# Redundancy.net
KiCad netlist of a schematic drawn in EAGLE
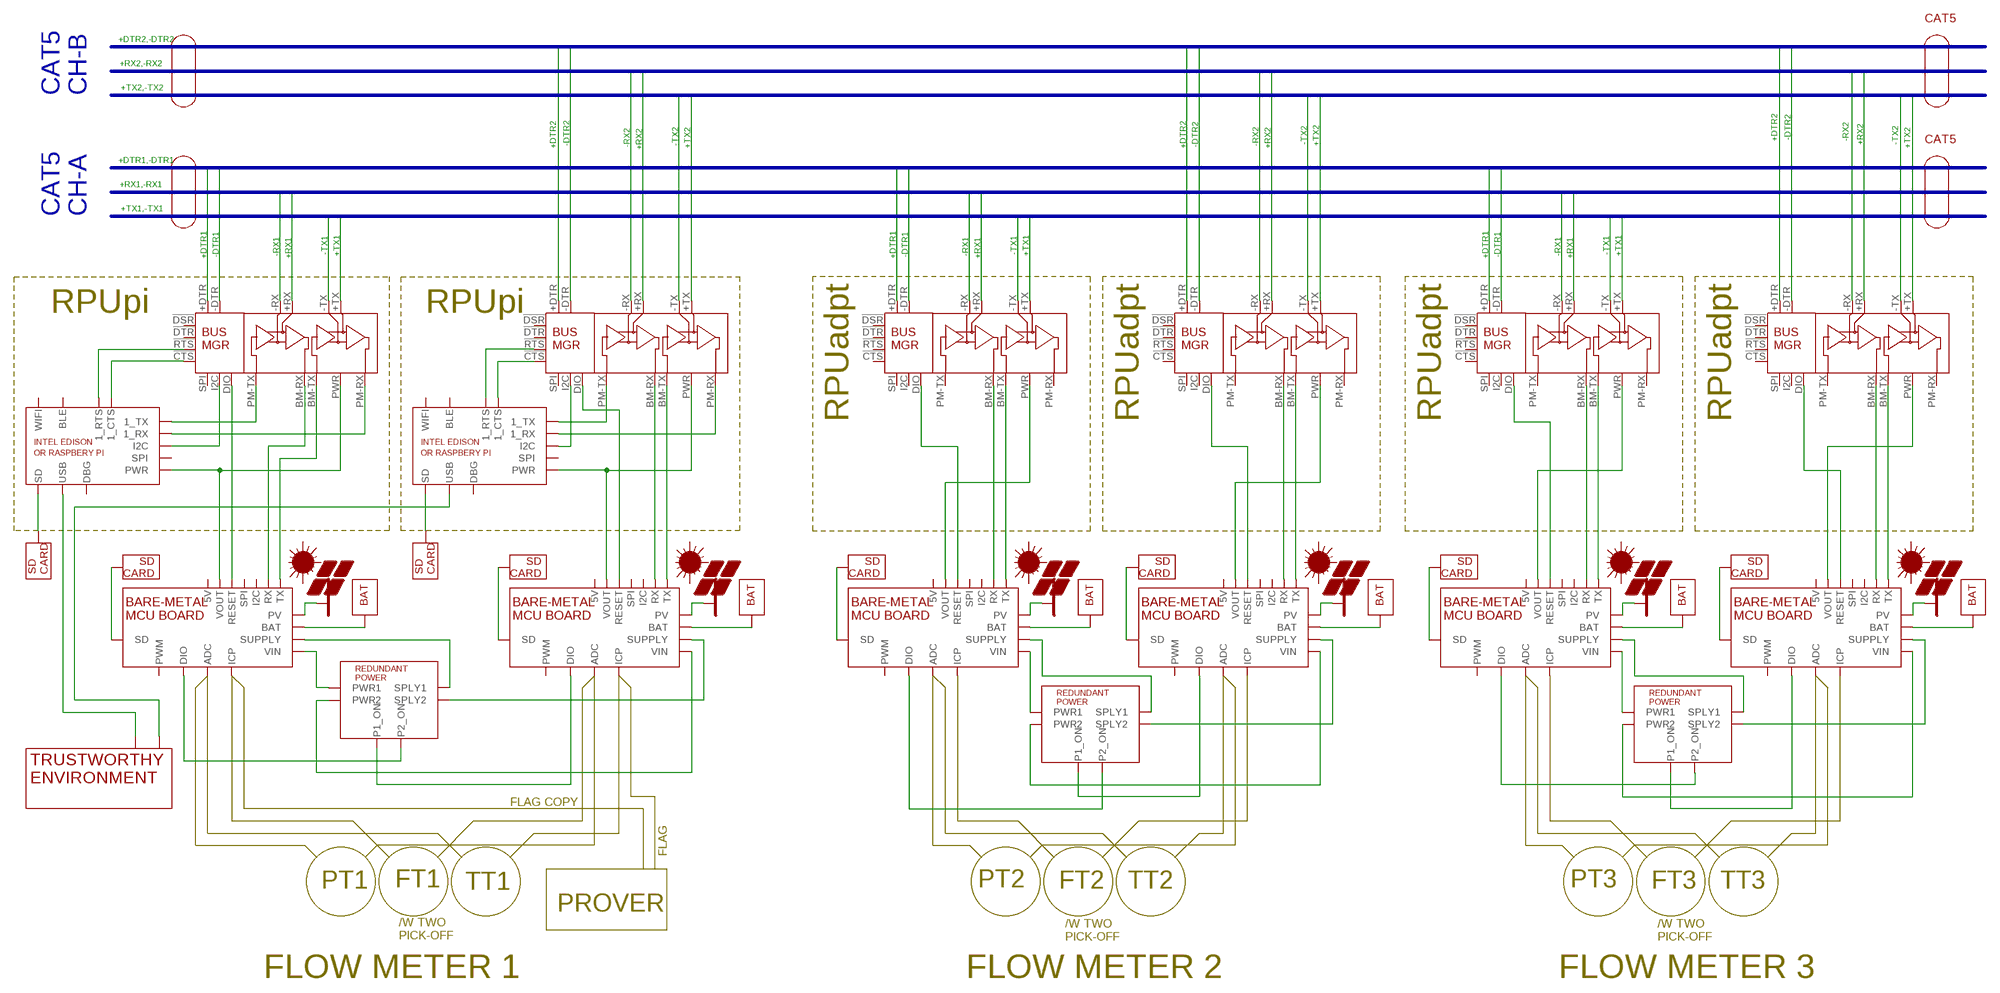
[diagram p0: schematic, sheet 1]

(export (version "E")
  (design (tool "Eeschema 10.0.6"))
  (components
    (comp (ref "BM1")
      (value "BARE-METAL")
      (footprint "eagle-import:NA-20")
      (libsource (lib "eagle-import") (part "BARE-METAL"))
    )
    (comp (ref "BM2")
      (value "BARE-METAL")
      (footprint "eagle-import:NA-20")
      (libsource (lib "eagle-import") (part "BARE-METAL"))
    )
    (comp (ref "BM3")
      (value "BARE-METAL")
      (footprint "eagle-import:NA-20")
      (libsource (lib "eagle-import") (part "BARE-METAL"))
    )
    (comp (ref "BM4")
      (value "BARE-METAL")
      (footprint "eagle-import:NA-20")
      (libsource (lib "eagle-import") (part "BARE-METAL"))
    )
    (comp (ref "BM5")
      (value "BARE-METAL")
      (footprint "eagle-import:NA-20")
      (libsource (lib "eagle-import") (part "BARE-METAL"))
    )
    (comp (ref "BM6")
      (value "BARE-METAL")
      (footprint "eagle-import:NA-20")
      (libsource (lib "eagle-import") (part "BARE-METAL"))
    )
    (comp (ref "PM1")
      (value "TRUSTWORTHY")
      (footprint "eagle-import:NA-20")
      (libsource (lib "eagle-import") (part "TRUSTWORTHY"))
    )
    (comp (ref "PV1")
      (value "PV")
      (footprint "eagle-import:NA-20")
      (libsource (lib "eagle-import") (part "PV"))
    )
    (comp (ref "PV2")
      (value "PV")
      (footprint "eagle-import:NA-20")
      (libsource (lib "eagle-import") (part "PV"))
    )
    (comp (ref "PV3")
      (value "PV")
      (footprint "eagle-import:NA-20")
      (libsource (lib "eagle-import") (part "PV"))
    )
    (comp (ref "PV4")
      (value "PV")
      (footprint "eagle-import:NA-20")
      (libsource (lib "eagle-import") (part "PV"))
    )
    (comp (ref "PV5")
      (value "PV")
      (footprint "eagle-import:NA-20")
      (libsource (lib "eagle-import") (part "PV"))
    )
    (comp (ref "PV6")
      (value "PV")
      (footprint "eagle-import:NA-20")
      (libsource (lib "eagle-import") (part "PV"))
    )
    (comp (ref "SD1")
      (value "SD")
      (footprint "eagle-import:NA-20")
      (libsource (lib "eagle-import") (part "SD"))
    )
    (comp (ref "SD2")
      (value "SD")
      (footprint "eagle-import:NA-20")
      (libsource (lib "eagle-import") (part "SD"))
    )
    (comp (ref "SD3")
      (value "SD")
      (footprint "eagle-import:NA-20")
      (libsource (lib "eagle-import") (part "SD"))
    )
    (comp (ref "SD4")
      (value "SD")
      (footprint "eagle-import:NA-20")
      (libsource (lib "eagle-import") (part "SD"))
    )
    (comp (ref "SD5")
      (value "SD")
      (footprint "eagle-import:NA-20")
      (libsource (lib "eagle-import") (part "SD"))
    )
    (comp (ref "SD6")
      (value "SD")
      (footprint "eagle-import:NA-20")
      (libsource (lib "eagle-import") (part "SD"))
    )
    (comp (ref "SD7")
      (value "SD")
      (footprint "eagle-import:NA-20")
      (libsource (lib "eagle-import") (part "SD"))
    )
    (comp (ref "SD8")
      (value "SD")
      (footprint "eagle-import:NA-20")
      (libsource (lib "eagle-import") (part "SD"))
    )
    (comp (ref "U$1")
      (value "BUS_MGR")
      (footprint "eagle-import:NA-10_WITH_RPU_NAMES")
      (libsource (lib "eagle-import") (part "BUS_MGR"))
    )
    (comp (ref "U$2")
      (value "BUS_MGR")
      (footprint "eagle-import:NA-10_WITH_RPU_NAMES")
      (libsource (lib "eagle-import") (part "BUS_MGR"))
    )
    (comp (ref "U$3")
      (value "BUS_MGR")
      (footprint "eagle-import:NA-10_WITH_RPU_NAMES")
      (libsource (lib "eagle-import") (part "BUS_MGR"))
    )
    (comp (ref "U$4")
      (value "BUS_MGR")
      (footprint "eagle-import:NA-10_WITH_RPU_NAMES")
      (libsource (lib "eagle-import") (part "BUS_MGR"))
    )
    (comp (ref "U$5")
      (value "EDISON")
      (footprint "eagle-import:NA-20")
      (libsource (lib "eagle-import") (part "EDISON"))
    )
    (comp (ref "U$6")
      (value "EDISON")
      (footprint "eagle-import:NA-20")
      (libsource (lib "eagle-import") (part "EDISON"))
    )
    (comp (ref "U$7")
      (value "BAT")
      (footprint "eagle-import:NA-20")
      (libsource (lib "eagle-import") (part "BAT"))
    )
    (comp (ref "U$8")
      (value "BAT")
      (footprint "eagle-import:NA-20")
      (libsource (lib "eagle-import") (part "BAT"))
    )
    (comp (ref "U$9")
      (value "BAT")
      (footprint "eagle-import:NA-20")
      (libsource (lib "eagle-import") (part "BAT"))
    )
    (comp (ref "U$10")
      (value "BAT")
      (footprint "eagle-import:NA-20")
      (libsource (lib "eagle-import") (part "BAT"))
    )
    (comp (ref "U$11")
      (value "BUS_MGR")
      (footprint "eagle-import:NA-10_WITH_RPU_NAMES")
      (libsource (lib "eagle-import") (part "BUS_MGR"))
    )
    (comp (ref "U$12")
      (value "BUS_MGR")
      (footprint "eagle-import:NA-10_WITH_RPU_NAMES")
      (libsource (lib "eagle-import") (part "BUS_MGR"))
    )
    (comp (ref "U$13")
      (value "BAT")
      (footprint "eagle-import:NA-20")
      (libsource (lib "eagle-import") (part "BAT"))
    )
    (comp (ref "U$14")
      (value "BAT")
      (footprint "eagle-import:NA-20")
      (libsource (lib "eagle-import") (part "BAT"))
    )
    (comp (ref "U$15")
      (value "REDUNDANT_PWR")
      (footprint "eagle-import:NA-20")
      (libsource (lib "eagle-import") (part "REDUNDANT_PWR"))
    )
    (comp (ref "U$16")
      (value "REDUNDANT_PWR")
      (footprint "eagle-import:NA-20")
      (libsource (lib "eagle-import") (part "REDUNDANT_PWR"))
    )
    (comp (ref "U$17")
      (value "REDUNDANT_PWR")
      (footprint "eagle-import:NA-20")
      (libsource (lib "eagle-import") (part "REDUNDANT_PWR"))
    )
  )
  (nets
    (net (code "1") (name "/+DTR1") (class "Default")
      (node (ref "U$1") (pin "+DTR") (pinfunction "+DTR_+DTR") (pintype "bidirectional"))
      (node (ref "U$11") (pin "+DTR") (pinfunction "+DTR_+DTR") (pintype "bidirectional"))
      (node (ref "U$3") (pin "+DTR") (pinfunction "+DTR_+DTR") (pintype "bidirectional"))
    )
    (net (code "2") (name "/+DTR2") (class "Default")
      (node (ref "U$12") (pin "+DTR") (pinfunction "+DTR_+DTR") (pintype "bidirectional"))
      (node (ref "U$2") (pin "+DTR") (pinfunction "+DTR_+DTR") (pintype "bidirectional"))
      (node (ref "U$4") (pin "+DTR") (pinfunction "+DTR_+DTR") (pintype "bidirectional"))
    )
    (net (code "3") (name "/+RX1") (class "Default")
      (node (ref "U$1") (pin "+RX") (pinfunction "+RX_+RX") (pintype "bidirectional"))
      (node (ref "U$11") (pin "+RX") (pinfunction "+RX_+RX") (pintype "bidirectional"))
      (node (ref "U$3") (pin "+RX") (pinfunction "+RX_+RX") (pintype "bidirectional"))
    )
    (net (code "4") (name "/+RX2") (class "Default")
      (node (ref "U$12") (pin "+RX") (pinfunction "+RX_+RX") (pintype "bidirectional"))
      (node (ref "U$2") (pin "+RX") (pinfunction "+RX_+RX") (pintype "bidirectional"))
      (node (ref "U$4") (pin "+RX") (pinfunction "+RX_+RX") (pintype "bidirectional"))
    )
    (net (code "5") (name "/+TX1") (class "Default")
      (node (ref "U$1") (pin "+TX") (pinfunction "+TX_+TX") (pintype "bidirectional"))
      (node (ref "U$11") (pin "+TX") (pinfunction "+TX_+TX") (pintype "bidirectional"))
      (node (ref "U$3") (pin "+TX") (pinfunction "+TX_+TX") (pintype "bidirectional"))
    )
    (net (code "6") (name "/+TX2") (class "Default")
      (node (ref "U$12") (pin "+TX") (pinfunction "+TX_+TX") (pintype "bidirectional"))
      (node (ref "U$2") (pin "+TX") (pinfunction "+TX_+TX") (pintype "bidirectional"))
      (node (ref "U$4") (pin "+TX") (pinfunction "+TX_+TX") (pintype "bidirectional"))
    )
    (net (code "7") (name "/-DTR1") (class "Default")
      (node (ref "U$1") (pin "-DTR") (pinfunction "-DTR_-DTR") (pintype "bidirectional"))
      (node (ref "U$11") (pin "-DTR") (pinfunction "-DTR_-DTR") (pintype "bidirectional"))
      (node (ref "U$3") (pin "-DTR") (pinfunction "-DTR_-DTR") (pintype "bidirectional"))
    )
    (net (code "8") (name "/-DTR2") (class "Default")
      (node (ref "U$12") (pin "-DTR") (pinfunction "-DTR_-DTR") (pintype "bidirectional"))
      (node (ref "U$2") (pin "-DTR") (pinfunction "-DTR_-DTR") (pintype "bidirectional"))
      (node (ref "U$4") (pin "-DTR") (pinfunction "-DTR_-DTR") (pintype "bidirectional"))
    )
    (net (code "9") (name "/-RX1") (class "Default")
      (node (ref "U$1") (pin "-RX") (pinfunction "-RX_-RX") (pintype "bidirectional"))
      (node (ref "U$11") (pin "-RX") (pinfunction "-RX_-RX") (pintype "bidirectional"))
      (node (ref "U$3") (pin "-RX") (pinfunction "-RX_-RX") (pintype "bidirectional"))
    )
    (net (code "10") (name "/-RX2") (class "Default")
      (node (ref "U$12") (pin "-RX") (pinfunction "-RX_-RX") (pintype "bidirectional"))
      (node (ref "U$2") (pin "-RX") (pinfunction "-RX_-RX") (pintype "bidirectional"))
      (node (ref "U$4") (pin "-RX") (pinfunction "-RX_-RX") (pintype "bidirectional"))
    )
    (net (code "11") (name "/-TX1") (class "Default")
      (node (ref "U$1") (pin "-TX") (pinfunction "-TX_-TX") (pintype "bidirectional"))
      (node (ref "U$11") (pin "-TX") (pinfunction "-TX_-TX") (pintype "bidirectional"))
      (node (ref "U$3") (pin "-TX") (pinfunction "-TX_-TX") (pintype "bidirectional"))
    )
    (net (code "12") (name "/-TX2") (class "Default")
      (node (ref "U$12") (pin "-TX") (pinfunction "-TX_-TX") (pintype "bidirectional"))
      (node (ref "U$2") (pin "-TX") (pinfunction "-TX_-TX") (pintype "bidirectional"))
      (node (ref "U$4") (pin "-TX") (pinfunction "-TX_-TX") (pintype "bidirectional"))
    )
    (net (code "19") (name "Net-(BM1-BAT)") (class "Default")
      (node (ref "BM1") (pin "6") (pinfunction "BAT_6") (pintype "bidirectional"))
      (node (ref "U$10") (pin "1") (pinfunction "BAT_PWR_1") (pintype "bidirectional"))
    )
    (net (code "20") (name "Net-(BM1-DIO)") (class "Default")
      (node (ref "BM1") (pin "9") (pinfunction "DIO_9") (pintype "bidirectional"))
      (node (ref "U$16") (pin "1") (pinfunction "P1_ON_1") (pintype "input"))
    )
    (net (code "21") (name "Net-(BM1-PV)") (class "Default")
      (node (ref "BM1") (pin "5") (pinfunction "PV_5") (pintype "bidirectional"))
      (node (ref "PV4") (pin "1") (pinfunction "PV_PWR_1") (pintype "bidirectional"))
    )
    (net (code "22") (name "Net-(BM1-RESET)") (class "Default")
      (node (ref "BM1") (pin "13") (pinfunction "RESET_13") (pintype "bidirectional"))
      (node (ref "U$4") (pin "DIO") (pinfunction "DIO_DIO") (pintype "bidirectional"))
    )
    (net (code "23") (name "Net-(BM1-RX)") (class "Default")
      (node (ref "BM1") (pin "2") (pinfunction "RX_2") (pintype "bidirectional"))
      (node (ref "U$4") (pin "BM-RX") (pinfunction "BM_RX_BM-RX") (pintype "bidirectional"))
    )
    (net (code "24") (name "Net-(BM1-SD)") (class "Default")
      (node (ref "BM1") (pin "11") (pinfunction "SD_11") (pintype "bidirectional"))
      (node (ref "SD4") (pin "1") (pinfunction "PV_PWR_1") (pintype "bidirectional"))
    )
    (net (code "25") (name "Net-(BM1-SUPPLY)") (class "Default")
      (node (ref "BM1") (pin "14") (pinfunction "SUPPLY_14") (pintype "bidirectional"))
      (node (ref "U$16") (pin "6") (pinfunction "SPLY2_6") (pintype "bidirectional"))
    )
    (net (code "26") (name "Net-(BM1-TX)") (class "Default")
      (node (ref "BM1") (pin "1") (pinfunction "TX_1") (pintype "bidirectional"))
      (node (ref "U$4") (pin "BM-TX") (pinfunction "BM_TX_BM-TX") (pintype "bidirectional"))
    )
    (net (code "27") (name "Net-(BM1-VIN)") (class "Default")
      (node (ref "BM1") (pin "16") (pinfunction "VIN_16") (pintype "bidirectional"))
      (node (ref "U$16") (pin "4") (pinfunction "PWR2_4") (pintype "bidirectional"))
    )
    (net (code "28") (name "Net-(BM1-VOUT)") (class "Default")
      (node (ref "BM1") (pin "12") (pinfunction "VOUT_12") (pintype "bidirectional"))
      (node (ref "U$4") (pin "PWR") (pinfunction "PWR_PWR") (pintype "bidirectional"))
    )
    (net (code "29") (name "Net-(BM2-BAT)") (class "Default")
      (node (ref "BM2") (pin "6") (pinfunction "BAT_6") (pintype "bidirectional"))
      (node (ref "U$9") (pin "1") (pinfunction "BAT_PWR_1") (pintype "bidirectional"))
    )
    (net (code "30") (name "Net-(BM2-DIO)") (class "Default")
      (node (ref "BM2") (pin "9") (pinfunction "DIO_9") (pintype "bidirectional"))
      (node (ref "U$16") (pin "2") (pinfunction "P2_ON_2") (pintype "input"))
    )
    (net (code "31") (name "Net-(BM2-PV)") (class "Default")
      (node (ref "BM2") (pin "5") (pinfunction "PV_5") (pintype "bidirectional"))
      (node (ref "PV3") (pin "1") (pinfunction "PV_PWR_1") (pintype "bidirectional"))
    )
    (net (code "32") (name "Net-(BM2-RESET)") (class "Default")
      (node (ref "BM2") (pin "13") (pinfunction "RESET_13") (pintype "bidirectional"))
      (node (ref "U$3") (pin "DIO") (pinfunction "DIO_DIO") (pintype "bidirectional"))
    )
    (net (code "33") (name "Net-(BM2-RX)") (class "Default")
      (node (ref "BM2") (pin "2") (pinfunction "RX_2") (pintype "bidirectional"))
      (node (ref "U$3") (pin "BM-RX") (pinfunction "BM_RX_BM-RX") (pintype "bidirectional"))
    )
    (net (code "34") (name "Net-(BM2-SD)") (class "Default")
      (node (ref "BM2") (pin "11") (pinfunction "SD_11") (pintype "bidirectional"))
      (node (ref "SD3") (pin "1") (pinfunction "PV_PWR_1") (pintype "bidirectional"))
    )
    (net (code "35") (name "Net-(BM2-SUPPLY)") (class "Default")
      (node (ref "BM2") (pin "14") (pinfunction "SUPPLY_14") (pintype "bidirectional"))
      (node (ref "U$16") (pin "5") (pinfunction "SPLY1_5") (pintype "bidirectional"))
    )
    (net (code "36") (name "Net-(BM2-TX)") (class "Default")
      (node (ref "BM2") (pin "1") (pinfunction "TX_1") (pintype "bidirectional"))
      (node (ref "U$3") (pin "BM-TX") (pinfunction "BM_TX_BM-TX") (pintype "bidirectional"))
    )
    (net (code "37") (name "Net-(BM2-VIN)") (class "Default")
      (node (ref "BM2") (pin "16") (pinfunction "VIN_16") (pintype "bidirectional"))
      (node (ref "U$16") (pin "3") (pinfunction "PWR1_3") (pintype "bidirectional"))
    )
    (net (code "38") (name "Net-(BM2-VOUT)") (class "Default")
      (node (ref "BM2") (pin "12") (pinfunction "VOUT_12") (pintype "bidirectional"))
      (node (ref "U$3") (pin "PWR") (pinfunction "PWR_PWR") (pintype "bidirectional"))
    )
    (net (code "39") (name "Net-(BM3-BAT)") (class "Default")
      (node (ref "BM3") (pin "6") (pinfunction "BAT_6") (pintype "bidirectional"))
      (node (ref "U$8") (pin "1") (pinfunction "BAT_PWR_1") (pintype "bidirectional"))
    )
    (net (code "40") (name "Net-(BM3-DIO)") (class "Default")
      (node (ref "BM3") (pin "9") (pinfunction "DIO_9") (pintype "bidirectional"))
      (node (ref "U$15") (pin "1") (pinfunction "P1_ON_1") (pintype "input"))
    )
    (net (code "41") (name "Net-(BM3-PV)") (class "Default")
      (node (ref "BM3") (pin "5") (pinfunction "PV_5") (pintype "bidirectional"))
      (node (ref "PV2") (pin "1") (pinfunction "PV_PWR_1") (pintype "bidirectional"))
    )
    (net (code "42") (name "Net-(BM3-RESET)") (class "Default")
      (node (ref "BM3") (pin "13") (pinfunction "RESET_13") (pintype "bidirectional"))
      (node (ref "U$2") (pin "DIO") (pinfunction "DIO_DIO") (pintype "bidirectional"))
    )
    (net (code "43") (name "Net-(BM3-RX)") (class "Default")
      (node (ref "BM3") (pin "2") (pinfunction "RX_2") (pintype "bidirectional"))
      (node (ref "U$2") (pin "BM-RX") (pinfunction "BM_RX_BM-RX") (pintype "bidirectional"))
    )
    (net (code "44") (name "Net-(BM3-SD)") (class "Default")
      (node (ref "BM3") (pin "11") (pinfunction "SD_11") (pintype "bidirectional"))
      (node (ref "SD7") (pin "1") (pinfunction "PV_PWR_1") (pintype "bidirectional"))
    )
    (net (code "45") (name "Net-(BM3-SUPPLY)") (class "Default")
      (node (ref "BM3") (pin "14") (pinfunction "SUPPLY_14") (pintype "bidirectional"))
      (node (ref "U$15") (pin "6") (pinfunction "SPLY2_6") (pintype "bidirectional"))
    )
    (net (code "46") (name "Net-(BM3-TX)") (class "Default")
      (node (ref "BM3") (pin "1") (pinfunction "TX_1") (pintype "bidirectional"))
      (node (ref "U$2") (pin "BM-TX") (pinfunction "BM_TX_BM-TX") (pintype "bidirectional"))
    )
    (net (code "47") (name "Net-(BM3-VIN)") (class "Default")
      (node (ref "BM3") (pin "16") (pinfunction "VIN_16") (pintype "bidirectional"))
      (node (ref "U$15") (pin "4") (pinfunction "PWR2_4") (pintype "bidirectional"))
    )
    (net (code "48") (name "Net-(BM3-VOUT)") (class "Default")
      (node (ref "BM3") (pin "12") (pinfunction "VOUT_12") (pintype "bidirectional"))
      (node (ref "U$2") (pin "PWR") (pinfunction "PWR_PWR") (pintype "bidirectional"))
      (node (ref "U$6") (pin "12") (pinfunction "PWR_12") (pintype "bidirectional"))
    )
    (net (code "49") (name "Net-(BM4-BAT)") (class "Default")
      (node (ref "BM4") (pin "6") (pinfunction "BAT_6") (pintype "bidirectional"))
      (node (ref "U$7") (pin "1") (pinfunction "BAT_PWR_1") (pintype "bidirectional"))
    )
    (net (code "50") (name "Net-(BM4-DIO)") (class "Default")
      (node (ref "BM4") (pin "9") (pinfunction "DIO_9") (pintype "bidirectional"))
      (node (ref "U$15") (pin "2") (pinfunction "P2_ON_2") (pintype "input"))
    )
    (net (code "51") (name "Net-(BM4-PV)") (class "Default")
      (node (ref "BM4") (pin "5") (pinfunction "PV_5") (pintype "bidirectional"))
      (node (ref "PV1") (pin "1") (pinfunction "PV_PWR_1") (pintype "bidirectional"))
    )
    (net (code "52") (name "Net-(BM4-RESET)") (class "Default")
      (node (ref "BM4") (pin "13") (pinfunction "RESET_13") (pintype "bidirectional"))
      (node (ref "U$1") (pin "DIO") (pinfunction "DIO_DIO") (pintype "bidirectional"))
    )
    (net (code "53") (name "Net-(BM4-RX)") (class "Default")
      (node (ref "BM4") (pin "2") (pinfunction "RX_2") (pintype "bidirectional"))
      (node (ref "U$1") (pin "BM-RX") (pinfunction "BM_RX_BM-RX") (pintype "bidirectional"))
    )
    (net (code "54") (name "Net-(BM4-SD)") (class "Default")
      (node (ref "BM4") (pin "11") (pinfunction "SD_11") (pintype "bidirectional"))
      (node (ref "SD8") (pin "1") (pinfunction "PV_PWR_1") (pintype "bidirectional"))
    )
    (net (code "55") (name "Net-(BM4-SUPPLY)") (class "Default")
      (node (ref "BM4") (pin "14") (pinfunction "SUPPLY_14") (pintype "bidirectional"))
      (node (ref "U$15") (pin "5") (pinfunction "SPLY1_5") (pintype "bidirectional"))
    )
    (net (code "56") (name "Net-(BM4-TX)") (class "Default")
      (node (ref "BM4") (pin "1") (pinfunction "TX_1") (pintype "bidirectional"))
      (node (ref "U$1") (pin "BM-TX") (pinfunction "BM_TX_BM-TX") (pintype "bidirectional"))
    )
    (net (code "57") (name "Net-(BM4-VIN)") (class "Default")
      (node (ref "BM4") (pin "16") (pinfunction "VIN_16") (pintype "bidirectional"))
      (node (ref "U$15") (pin "3") (pinfunction "PWR1_3") (pintype "bidirectional"))
    )
    (net (code "58") (name "Net-(BM4-VOUT)") (class "Default")
      (node (ref "BM4") (pin "12") (pinfunction "VOUT_12") (pintype "bidirectional"))
      (node (ref "U$1") (pin "PWR") (pinfunction "PWR_PWR") (pintype "bidirectional"))
      (node (ref "U$5") (pin "12") (pinfunction "PWR_12") (pintype "bidirectional"))
    )
    (net (code "59") (name "Net-(BM5-BAT)") (class "Default")
      (node (ref "BM5") (pin "6") (pinfunction "BAT_6") (pintype "bidirectional"))
      (node (ref "U$14") (pin "1") (pinfunction "BAT_PWR_1") (pintype "bidirectional"))
    )
    (net (code "60") (name "Net-(BM5-DIO)") (class "Default")
      (node (ref "BM5") (pin "9") (pinfunction "DIO_9") (pintype "bidirectional"))
      (node (ref "U$17") (pin "1") (pinfunction "P1_ON_1") (pintype "input"))
    )
    (net (code "61") (name "Net-(BM5-PV)") (class "Default")
      (node (ref "BM5") (pin "5") (pinfunction "PV_5") (pintype "bidirectional"))
      (node (ref "PV6") (pin "1") (pinfunction "PV_PWR_1") (pintype "bidirectional"))
    )
    (net (code "62") (name "Net-(BM5-RESET)") (class "Default")
      (node (ref "BM5") (pin "13") (pinfunction "RESET_13") (pintype "bidirectional"))
      (node (ref "U$12") (pin "DIO") (pinfunction "DIO_DIO") (pintype "bidirectional"))
    )
    (net (code "63") (name "Net-(BM5-RX)") (class "Default")
      (node (ref "BM5") (pin "2") (pinfunction "RX_2") (pintype "bidirectional"))
      (node (ref "U$12") (pin "BM-RX") (pinfunction "BM_RX_BM-RX") (pintype "bidirectional"))
    )
    (net (code "64") (name "Net-(BM5-SD)") (class "Default")
      (node (ref "BM5") (pin "11") (pinfunction "SD_11") (pintype "bidirectional"))
      (node (ref "SD6") (pin "1") (pinfunction "PV_PWR_1") (pintype "bidirectional"))
    )
    (net (code "65") (name "Net-(BM5-SUPPLY)") (class "Default")
      (node (ref "BM5") (pin "14") (pinfunction "SUPPLY_14") (pintype "bidirectional"))
      (node (ref "U$17") (pin "6") (pinfunction "SPLY2_6") (pintype "bidirectional"))
    )
    (net (code "66") (name "Net-(BM5-TX)") (class "Default")
      (node (ref "BM5") (pin "1") (pinfunction "TX_1") (pintype "bidirectional"))
      (node (ref "U$12") (pin "BM-TX") (pinfunction "BM_TX_BM-TX") (pintype "bidirectional"))
    )
    (net (code "67") (name "Net-(BM5-VIN)") (class "Default")
      (node (ref "BM5") (pin "16") (pinfunction "VIN_16") (pintype "bidirectional"))
      (node (ref "U$17") (pin "4") (pinfunction "PWR2_4") (pintype "bidirectional"))
    )
    (net (code "68") (name "Net-(BM5-VOUT)") (class "Default")
      (node (ref "BM5") (pin "12") (pinfunction "VOUT_12") (pintype "bidirectional"))
      (node (ref "U$12") (pin "PWR") (pinfunction "PWR_PWR") (pintype "bidirectional"))
    )
    (net (code "69") (name "Net-(BM6-BAT)") (class "Default")
      (node (ref "BM6") (pin "6") (pinfunction "BAT_6") (pintype "bidirectional"))
      (node (ref "U$13") (pin "1") (pinfunction "BAT_PWR_1") (pintype "bidirectional"))
    )
    (net (code "70") (name "Net-(BM6-DIO)") (class "Default")
      (node (ref "BM6") (pin "9") (pinfunction "DIO_9") (pintype "bidirectional"))
      (node (ref "U$17") (pin "2") (pinfunction "P2_ON_2") (pintype "input"))
    )
    (net (code "71") (name "Net-(BM6-PV)") (class "Default")
      (node (ref "BM6") (pin "5") (pinfunction "PV_5") (pintype "bidirectional"))
      (node (ref "PV5") (pin "1") (pinfunction "PV_PWR_1") (pintype "bidirectional"))
    )
    (net (code "72") (name "Net-(BM6-RESET)") (class "Default")
      (node (ref "BM6") (pin "13") (pinfunction "RESET_13") (pintype "bidirectional"))
      (node (ref "U$11") (pin "DIO") (pinfunction "DIO_DIO") (pintype "bidirectional"))
    )
    (net (code "73") (name "Net-(BM6-RX)") (class "Default")
      (node (ref "BM6") (pin "2") (pinfunction "RX_2") (pintype "bidirectional"))
      (node (ref "U$11") (pin "BM-RX") (pinfunction "BM_RX_BM-RX") (pintype "bidirectional"))
    )
    (net (code "74") (name "Net-(BM6-SD)") (class "Default")
      (node (ref "BM6") (pin "11") (pinfunction "SD_11") (pintype "bidirectional"))
      (node (ref "SD5") (pin "1") (pinfunction "PV_PWR_1") (pintype "bidirectional"))
    )
    (net (code "75") (name "Net-(BM6-SUPPLY)") (class "Default")
      (node (ref "BM6") (pin "14") (pinfunction "SUPPLY_14") (pintype "bidirectional"))
      (node (ref "U$17") (pin "5") (pinfunction "SPLY1_5") (pintype "bidirectional"))
    )
    (net (code "76") (name "Net-(BM6-TX)") (class "Default")
      (node (ref "BM6") (pin "1") (pinfunction "TX_1") (pintype "bidirectional"))
      (node (ref "U$11") (pin "BM-TX") (pinfunction "BM_TX_BM-TX") (pintype "bidirectional"))
    )
    (net (code "77") (name "Net-(BM6-VIN)") (class "Default")
      (node (ref "BM6") (pin "16") (pinfunction "VIN_16") (pintype "bidirectional"))
      (node (ref "U$17") (pin "3") (pinfunction "PWR1_3") (pintype "bidirectional"))
    )
    (net (code "78") (name "Net-(BM6-VOUT)") (class "Default")
      (node (ref "BM6") (pin "12") (pinfunction "VOUT_12") (pintype "bidirectional"))
      (node (ref "U$11") (pin "PWR") (pinfunction "PWR_PWR") (pintype "bidirectional"))
    )
    (net (code "79") (name "Net-(PM1-RX)") (class "Default")
      (node (ref "PM1") (pin "1") (pinfunction "RX_1") (pintype "bidirectional"))
      (node (ref "U$5") (pin "11") (pinfunction "USB_11") (pintype "input"))
    )
    (net (code "80") (name "Net-(PM1-TX)") (class "Default")
      (node (ref "PM1") (pin "2") (pinfunction "TX_2") (pintype "bidirectional"))
      (node (ref "U$6") (pin "11") (pinfunction "USB_11") (pintype "input"))
    )
    (net (code "81") (name "Net-(SD1-PV_PWR)") (class "Default")
      (node (ref "SD1") (pin "1") (pinfunction "PV_PWR_1") (pintype "bidirectional"))
      (node (ref "U$5") (pin "9") (pinfunction "SD_9") (pintype "input"))
    )
    (net (code "82") (name "Net-(SD2-PV_PWR)") (class "Default")
      (node (ref "SD2") (pin "1") (pinfunction "PV_PWR_1") (pintype "bidirectional"))
      (node (ref "U$6") (pin "9") (pinfunction "SD_9") (pintype "input"))
    )
    (net (code "83") (name "Net-(U$1-PM_RX)") (class "Default")
      (node (ref "U$1") (pin "PM-RX") (pinfunction "PM_RX_PM-RX") (pintype "bidirectional"))
      (node (ref "U$5") (pin "3") (pinfunction "1_RX_3") (pintype "bidirectional"))
    )
    (net (code "84") (name "Net-(U$1-PM_TX)") (class "Default")
      (node (ref "U$1") (pin "PM-TX") (pinfunction "PM_TX_PM-TX") (pintype "bidirectional"))
      (node (ref "U$5") (pin "4") (pinfunction "1_TX_4") (pintype "bidirectional"))
    )
    (net (code "85") (name "Net-(U$1-~{CTS})") (class "Default")
      (node (ref "U$1") (pin "!CTS") (pinfunction "~{CTS}_!CTS") (pintype "bidirectional"))
      (node (ref "U$5") (pin "1") (pinfunction "1_CTS_1") (pintype "input"))
    )
    (net (code "86") (name "Net-(U$1-~{RTS})") (class "Default")
      (node (ref "U$1") (pin "!RTS") (pinfunction "~{RTS}_!RTS") (pintype "bidirectional"))
      (node (ref "U$5") (pin "2") (pinfunction "1_RTS_2") (pintype "input"))
    )
    (net (code "87") (name "Net-(U$2-PM_RX)") (class "Default")
      (node (ref "U$2") (pin "PM-RX") (pinfunction "PM_RX_PM-RX") (pintype "bidirectional"))
      (node (ref "U$6") (pin "3") (pinfunction "1_RX_3") (pintype "bidirectional"))
    )
    (net (code "88") (name "Net-(U$2-PM_TX)") (class "Default")
      (node (ref "U$2") (pin "PM-TX") (pinfunction "PM_TX_PM-TX") (pintype "bidirectional"))
      (node (ref "U$6") (pin "4") (pinfunction "1_TX_4") (pintype "bidirectional"))
    )
    (net (code "89") (name "Net-(U$2-~{CTS})") (class "Default")
      (node (ref "U$2") (pin "!CTS") (pinfunction "~{CTS}_!CTS") (pintype "bidirectional"))
      (node (ref "U$6") (pin "1") (pinfunction "1_CTS_1") (pintype "input"))
    )
    (net (code "90") (name "Net-(U$2-~{RTS})") (class "Default")
      (node (ref "U$2") (pin "!RTS") (pinfunction "~{RTS}_!RTS") (pintype "bidirectional"))
      (node (ref "U$6") (pin "2") (pinfunction "1_RTS_2") (pintype "input"))
    )
    (net (code "91") (name "Net-(U$5-I2C)") (class "Default")
      (node (ref "U$1") (pin "I2C") (pinfunction "I2C_I2C") (pintype "bidirectional"))
      (node (ref "U$5") (pin "8") (pinfunction "I2C_8") (pintype "bidirectional"))
    )
    (net (code "92") (name "Net-(U$6-I2C)") (class "Default")
      (node (ref "U$2") (pin "I2C") (pinfunction "I2C_I2C") (pintype "bidirectional"))
      (node (ref "U$6") (pin "8") (pinfunction "I2C_8") (pintype "bidirectional"))
    )
    (net (code "93") (name "unconnected-(BM1-5V-Pad15)") (class "Default")
      (node (ref "BM1") (pin "15") (pinfunction "5V_15") (pintype "bidirectional"))
    )
    (net (code "94") (name "unconnected-(BM1-ADC-Pad8)") (class "Default")
      (node (ref "BM1") (pin "8") (pinfunction "ADC_8") (pintype "bidirectional"))
    )
    (net (code "95") (name "unconnected-(BM1-I2C-Pad3)") (class "Default")
      (node (ref "BM1") (pin "3") (pinfunction "I2C_3") (pintype "bidirectional"))
    )
    (net (code "96") (name "unconnected-(BM1-ICP-Pad7)") (class "Default")
      (node (ref "BM1") (pin "7") (pinfunction "ICP_7") (pintype "bidirectional"))
    )
    (net (code "97") (name "unconnected-(BM1-PWM-Pad10)") (class "Default")
      (node (ref "BM1") (pin "10") (pinfunction "PWM_10") (pintype "bidirectional"))
    )
    (net (code "98") (name "unconnected-(BM1-SPI-Pad4)") (class "Default")
      (node (ref "BM1") (pin "4") (pinfunction "SPI_4") (pintype "bidirectional"))
    )
    (net (code "99") (name "unconnected-(BM2-5V-Pad15)") (class "Default")
      (node (ref "BM2") (pin "15") (pinfunction "5V_15") (pintype "bidirectional"))
    )
    (net (code "100") (name "unconnected-(BM2-ADC-Pad8)") (class "Default")
      (node (ref "BM2") (pin "8") (pinfunction "ADC_8") (pintype "bidirectional"))
    )
    (net (code "101") (name "unconnected-(BM2-I2C-Pad3)") (class "Default")
      (node (ref "BM2") (pin "3") (pinfunction "I2C_3") (pintype "bidirectional"))
    )
    (net (code "102") (name "unconnected-(BM2-ICP-Pad7)") (class "Default")
      (node (ref "BM2") (pin "7") (pinfunction "ICP_7") (pintype "bidirectional"))
    )
    (net (code "103") (name "unconnected-(BM2-PWM-Pad10)") (class "Default")
      (node (ref "BM2") (pin "10") (pinfunction "PWM_10") (pintype "bidirectional"))
    )
    (net (code "104") (name "unconnected-(BM2-SPI-Pad4)") (class "Default")
      (node (ref "BM2") (pin "4") (pinfunction "SPI_4") (pintype "bidirectional"))
    )
    (net (code "105") (name "unconnected-(BM3-5V-Pad15)") (class "Default")
      (node (ref "BM3") (pin "15") (pinfunction "5V_15") (pintype "bidirectional"))
    )
    (net (code "106") (name "unconnected-(BM3-ADC-Pad8)") (class "Default")
      (node (ref "BM3") (pin "8") (pinfunction "ADC_8") (pintype "bidirectional"))
    )
    (net (code "107") (name "unconnected-(BM3-I2C-Pad3)") (class "Default")
      (node (ref "BM3") (pin "3") (pinfunction "I2C_3") (pintype "bidirectional"))
    )
    (net (code "108") (name "unconnected-(BM3-ICP-Pad7)") (class "Default")
      (node (ref "BM3") (pin "7") (pinfunction "ICP_7") (pintype "bidirectional"))
    )
    (net (code "109") (name "unconnected-(BM3-PWM-Pad10)") (class "Default")
      (node (ref "BM3") (pin "10") (pinfunction "PWM_10") (pintype "bidirectional"))
    )
    (net (code "110") (name "unconnected-(BM3-SPI-Pad4)") (class "Default")
      (node (ref "BM3") (pin "4") (pinfunction "SPI_4") (pintype "bidirectional"))
    )
    (net (code "111") (name "unconnected-(BM4-5V-Pad15)") (class "Default")
      (node (ref "BM4") (pin "15") (pinfunction "5V_15") (pintype "bidirectional"))
    )
    (net (code "112") (name "unconnected-(BM4-ADC-Pad8)") (class "Default")
      (node (ref "BM4") (pin "8") (pinfunction "ADC_8") (pintype "bidirectional"))
    )
    (net (code "113") (name "unconnected-(BM4-I2C-Pad3)") (class "Default")
      (node (ref "BM4") (pin "3") (pinfunction "I2C_3") (pintype "bidirectional"))
    )
    (net (code "114") (name "unconnected-(BM4-ICP-Pad7)") (class "Default")
      (node (ref "BM4") (pin "7") (pinfunction "ICP_7") (pintype "bidirectional"))
    )
    (net (code "115") (name "unconnected-(BM4-PWM-Pad10)") (class "Default")
      (node (ref "BM4") (pin "10") (pinfunction "PWM_10") (pintype "bidirectional"))
    )
    (net (code "116") (name "unconnected-(BM4-SPI-Pad4)") (class "Default")
      (node (ref "BM4") (pin "4") (pinfunction "SPI_4") (pintype "bidirectional"))
    )
    (net (code "117") (name "unconnected-(BM5-5V-Pad15)") (class "Default")
      (node (ref "BM5") (pin "15") (pinfunction "5V_15") (pintype "bidirectional"))
    )
    (net (code "118") (name "unconnected-(BM5-ADC-Pad8)") (class "Default")
      (node (ref "BM5") (pin "8") (pinfunction "ADC_8") (pintype "bidirectional"))
    )
    (net (code "119") (name "unconnected-(BM5-I2C-Pad3)") (class "Default")
      (node (ref "BM5") (pin "3") (pinfunction "I2C_3") (pintype "bidirectional"))
    )
    (net (code "120") (name "unconnected-(BM5-ICP-Pad7)") (class "Default")
      (node (ref "BM5") (pin "7") (pinfunction "ICP_7") (pintype "bidirectional"))
    )
    (net (code "121") (name "unconnected-(BM5-PWM-Pad10)") (class "Default")
      (node (ref "BM5") (pin "10") (pinfunction "PWM_10") (pintype "bidirectional"))
    )
    (net (code "122") (name "unconnected-(BM5-SPI-Pad4)") (class "Default")
      (node (ref "BM5") (pin "4") (pinfunction "SPI_4") (pintype "bidirectional"))
    )
    (net (code "123") (name "unconnected-(BM6-5V-Pad15)") (class "Default")
      (node (ref "BM6") (pin "15") (pinfunction "5V_15") (pintype "bidirectional"))
    )
    (net (code "124") (name "unconnected-(BM6-ADC-Pad8)") (class "Default")
      (node (ref "BM6") (pin "8") (pinfunction "ADC_8") (pintype "bidirectional"))
    )
    (net (code "125") (name "unconnected-(BM6-I2C-Pad3)") (class "Default")
      (node (ref "BM6") (pin "3") (pinfunction "I2C_3") (pintype "bidirectional"))
    )
    (net (code "126") (name "unconnected-(BM6-ICP-Pad7)") (class "Default")
      (node (ref "BM6") (pin "7") (pinfunction "ICP_7") (pintype "bidirectional"))
    )
    (net (code "127") (name "unconnected-(BM6-PWM-Pad10)") (class "Default")
      (node (ref "BM6") (pin "10") (pinfunction "PWM_10") (pintype "bidirectional"))
    )
    (net (code "128") (name "unconnected-(BM6-SPI-Pad4)") (class "Default")
      (node (ref "BM6") (pin "4") (pinfunction "SPI_4") (pintype "bidirectional"))
    )
    (net (code "129") (name "unconnected-(U$1-PadSPI)") (class "Default")
      (node (ref "U$1") (pin "SPI") (pinfunction "SPI_SPI") (pintype "bidirectional"))
    )
    (net (code "130") (name "unconnected-(U$1-~{DSR}-Pad!DSR)") (class "Default")
      (node (ref "U$1") (pin "!DSR") (pinfunction "~{DSR}_!DSR") (pintype "bidirectional"))
    )
    (net (code "131") (name "unconnected-(U$1-~{DTR}-Pad!DTR)") (class "Default")
      (node (ref "U$1") (pin "!DTR") (pinfunction "~{DTR}_!DTR") (pintype "bidirectional"))
    )
    (net (code "132") (name "unconnected-(U$2-PadSPI)") (class "Default")
      (node (ref "U$2") (pin "SPI") (pinfunction "SPI_SPI") (pintype "bidirectional"))
    )
    (net (code "133") (name "unconnected-(U$2-~{DSR}-Pad!DSR)") (class "Default")
      (node (ref "U$2") (pin "!DSR") (pinfunction "~{DSR}_!DSR") (pintype "bidirectional"))
    )
    (net (code "134") (name "unconnected-(U$2-~{DTR}-Pad!DTR)") (class "Default")
      (node (ref "U$2") (pin "!DTR") (pinfunction "~{DTR}_!DTR") (pintype "bidirectional"))
    )
    (net (code "135") (name "unconnected-(U$3-PM_RX-PadPM-RX)") (class "Default")
      (node (ref "U$3") (pin "PM-RX") (pinfunction "PM_RX_PM-RX") (pintype "bidirectional"))
    )
    (net (code "136") (name "unconnected-(U$3-PM_TX-PadPM-TX)") (class "Default")
      (node (ref "U$3") (pin "PM-TX") (pinfunction "PM_TX_PM-TX") (pintype "bidirectional"))
    )
    (net (code "137") (name "unconnected-(U$3-PadI2C)") (class "Default")
      (node (ref "U$3") (pin "I2C") (pinfunction "I2C_I2C") (pintype "bidirectional"))
    )
    (net (code "138") (name "unconnected-(U$3-PadSPI)") (class "Default")
      (node (ref "U$3") (pin "SPI") (pinfunction "SPI_SPI") (pintype "bidirectional"))
    )
    (net (code "139") (name "unconnected-(U$3-~{CTS}-Pad!CTS)") (class "Default")
      (node (ref "U$3") (pin "!CTS") (pinfunction "~{CTS}_!CTS") (pintype "bidirectional"))
    )
    (net (code "140") (name "unconnected-(U$3-~{DSR}-Pad!DSR)") (class "Default")
      (node (ref "U$3") (pin "!DSR") (pinfunction "~{DSR}_!DSR") (pintype "bidirectional"))
    )
    (net (code "141") (name "unconnected-(U$3-~{DTR}-Pad!DTR)") (class "Default")
      (node (ref "U$3") (pin "!DTR") (pinfunction "~{DTR}_!DTR") (pintype "bidirectional"))
    )
    (net (code "142") (name "unconnected-(U$3-~{RTS}-Pad!RTS)") (class "Default")
      (node (ref "U$3") (pin "!RTS") (pinfunction "~{RTS}_!RTS") (pintype "bidirectional"))
    )
    (net (code "143") (name "unconnected-(U$4-PM_RX-PadPM-RX)") (class "Default")
      (node (ref "U$4") (pin "PM-RX") (pinfunction "PM_RX_PM-RX") (pintype "bidirectional"))
    )
    (net (code "144") (name "unconnected-(U$4-PM_TX-PadPM-TX)") (class "Default")
      (node (ref "U$4") (pin "PM-TX") (pinfunction "PM_TX_PM-TX") (pintype "bidirectional"))
    )
    (net (code "145") (name "unconnected-(U$4-PadI2C)") (class "Default")
      (node (ref "U$4") (pin "I2C") (pinfunction "I2C_I2C") (pintype "bidirectional"))
    )
    (net (code "146") (name "unconnected-(U$4-PadSPI)") (class "Default")
      (node (ref "U$4") (pin "SPI") (pinfunction "SPI_SPI") (pintype "bidirectional"))
    )
    (net (code "147") (name "unconnected-(U$4-~{CTS}-Pad!CTS)") (class "Default")
      (node (ref "U$4") (pin "!CTS") (pinfunction "~{CTS}_!CTS") (pintype "bidirectional"))
    )
    (net (code "148") (name "unconnected-(U$4-~{DSR}-Pad!DSR)") (class "Default")
      (node (ref "U$4") (pin "!DSR") (pinfunction "~{DSR}_!DSR") (pintype "bidirectional"))
    )
    (net (code "149") (name "unconnected-(U$4-~{DTR}-Pad!DTR)") (class "Default")
      (node (ref "U$4") (pin "!DTR") (pinfunction "~{DTR}_!DTR") (pintype "bidirectional"))
    )
    (net (code "150") (name "unconnected-(U$4-~{RTS}-Pad!RTS)") (class "Default")
      (node (ref "U$4") (pin "!RTS") (pinfunction "~{RTS}_!RTS") (pintype "bidirectional"))
    )
    (net (code "151") (name "unconnected-(U$5-BLE-Pad6)") (class "Default")
      (node (ref "U$5") (pin "6") (pinfunction "BLE_6") (pintype "input"))
    )
    (net (code "152") (name "unconnected-(U$5-DBG-Pad7)") (class "Default")
      (node (ref "U$5") (pin "7") (pinfunction "DBG_7") (pintype "input"))
    )
    (net (code "153") (name "unconnected-(U$5-SPI-Pad10)") (class "Default")
      (node (ref "U$5") (pin "10") (pinfunction "SPI_10") (pintype "bidirectional"))
    )
    (net (code "154") (name "unconnected-(U$5-WIFI-Pad5)") (class "Default")
      (node (ref "U$5") (pin "5") (pinfunction "WIFI_5") (pintype "input"))
    )
    (net (code "155") (name "unconnected-(U$6-BLE-Pad6)") (class "Default")
      (node (ref "U$6") (pin "6") (pinfunction "BLE_6") (pintype "input"))
    )
    (net (code "156") (name "unconnected-(U$6-DBG-Pad7)") (class "Default")
      (node (ref "U$6") (pin "7") (pinfunction "DBG_7") (pintype "input"))
    )
    (net (code "157") (name "unconnected-(U$6-SPI-Pad10)") (class "Default")
      (node (ref "U$6") (pin "10") (pinfunction "SPI_10") (pintype "bidirectional"))
    )
    (net (code "158") (name "unconnected-(U$6-WIFI-Pad5)") (class "Default")
      (node (ref "U$6") (pin "5") (pinfunction "WIFI_5") (pintype "input"))
    )
    (net (code "159") (name "unconnected-(U$11-PM_RX-PadPM-RX)") (class "Default")
      (node (ref "U$11") (pin "PM-RX") (pinfunction "PM_RX_PM-RX") (pintype "bidirectional"))
    )
    (net (code "160") (name "unconnected-(U$11-PM_TX-PadPM-TX)") (class "Default")
      (node (ref "U$11") (pin "PM-TX") (pinfunction "PM_TX_PM-TX") (pintype "bidirectional"))
    )
    (net (code "161") (name "unconnected-(U$11-PadI2C)") (class "Default")
      (node (ref "U$11") (pin "I2C") (pinfunction "I2C_I2C") (pintype "bidirectional"))
    )
    (net (code "162") (name "unconnected-(U$11-PadSPI)") (class "Default")
      (node (ref "U$11") (pin "SPI") (pinfunction "SPI_SPI") (pintype "bidirectional"))
    )
    (net (code "163") (name "unconnected-(U$11-~{CTS}-Pad!CTS)") (class "Default")
      (node (ref "U$11") (pin "!CTS") (pinfunction "~{CTS}_!CTS") (pintype "bidirectional"))
    )
    (net (code "164") (name "unconnected-(U$11-~{DSR}-Pad!DSR)") (class "Default")
      (node (ref "U$11") (pin "!DSR") (pinfunction "~{DSR}_!DSR") (pintype "bidirectional"))
    )
    (net (code "165") (name "unconnected-(U$11-~{DTR}-Pad!DTR)") (class "Default")
      (node (ref "U$11") (pin "!DTR") (pinfunction "~{DTR}_!DTR") (pintype "bidirectional"))
    )
    (net (code "166") (name "unconnected-(U$11-~{RTS}-Pad!RTS)") (class "Default")
      (node (ref "U$11") (pin "!RTS") (pinfunction "~{RTS}_!RTS") (pintype "bidirectional"))
    )
    (net (code "167") (name "unconnected-(U$12-PM_RX-PadPM-RX)") (class "Default")
      (node (ref "U$12") (pin "PM-RX") (pinfunction "PM_RX_PM-RX") (pintype "bidirectional"))
    )
    (net (code "168") (name "unconnected-(U$12-PM_TX-PadPM-TX)") (class "Default")
      (node (ref "U$12") (pin "PM-TX") (pinfunction "PM_TX_PM-TX") (pintype "bidirectional"))
    )
    (net (code "169") (name "unconnected-(U$12-PadI2C)") (class "Default")
      (node (ref "U$12") (pin "I2C") (pinfunction "I2C_I2C") (pintype "bidirectional"))
    )
    (net (code "170") (name "unconnected-(U$12-PadSPI)") (class "Default")
      (node (ref "U$12") (pin "SPI") (pinfunction "SPI_SPI") (pintype "bidirectional"))
    )
    (net (code "171") (name "unconnected-(U$12-~{CTS}-Pad!CTS)") (class "Default")
      (node (ref "U$12") (pin "!CTS") (pinfunction "~{CTS}_!CTS") (pintype "bidirectional"))
    )
    (net (code "172") (name "unconnected-(U$12-~{DSR}-Pad!DSR)") (class "Default")
      (node (ref "U$12") (pin "!DSR") (pinfunction "~{DSR}_!DSR") (pintype "bidirectional"))
    )
    (net (code "173") (name "unconnected-(U$12-~{DTR}-Pad!DTR)") (class "Default")
      (node (ref "U$12") (pin "!DTR") (pinfunction "~{DTR}_!DTR") (pintype "bidirectional"))
    )
    (net (code "174") (name "unconnected-(U$12-~{RTS}-Pad!RTS)") (class "Default")
      (node (ref "U$12") (pin "!RTS") (pinfunction "~{RTS}_!RTS") (pintype "bidirectional"))
    )
  )
)
